# proyek_gempa_bumi.net
KiCad netlist of a schematic drawn in EAGLE
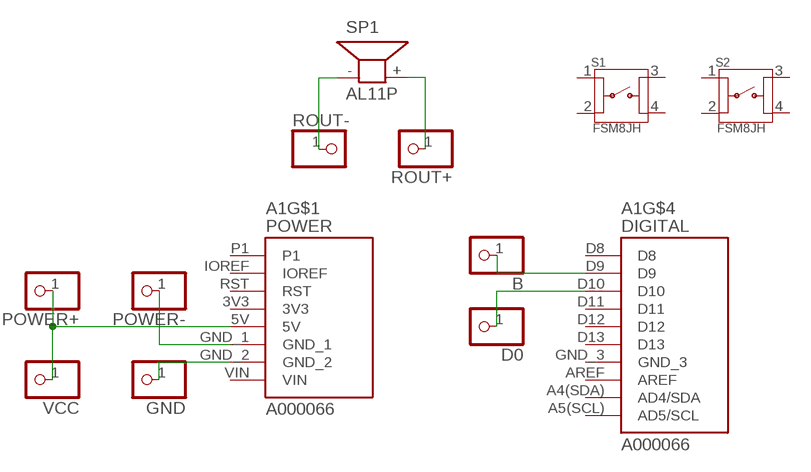
[diagram p0: schematic, sheet 1]

(export (version "E")
  (design (tool "Eeschema 10.0.6"))
  (components
    (comp (ref "A1")
      (value "A000066")
      (footprint "eagle-import:ARDUINO_A000066")
      (fields (field (name "MF") "Arduino") (field (name "MP") "ARDUINO UNO REV3"))
      (libsource (lib "eagle-import") (part "A000066"))
    )
    (comp (ref "B")
      (value "PINHD-1X1")
      (footprint "eagle-import:1X01")
      (libsource (lib "eagle-import") (part "PINHD-1X1"))
    )
    (comp (ref "D0")
      (value "PINHD-1X1")
      (footprint "eagle-import:1X01")
      (libsource (lib "eagle-import") (part "PINHD-1X1"))
    )
    (comp (ref "GND")
      (value "PINHD-1X1")
      (footprint "eagle-import:1X01")
      (libsource (lib "eagle-import") (part "PINHD-1X1"))
    )
    (comp (ref "POWER+")
      (value "PINHD-1X1")
      (footprint "eagle-import:1X01")
      (libsource (lib "eagle-import") (part "PINHD-1X1"))
    )
    (comp (ref "POWER-")
      (value "PINHD-1X1")
      (footprint "eagle-import:1X01")
      (libsource (lib "eagle-import") (part "PINHD-1X1"))
    )
    (comp (ref "ROUT+")
      (value "PINHD-1X1")
      (footprint "eagle-import:1X01")
      (libsource (lib "eagle-import") (part "PINHD-1X1"))
    )
    (comp (ref "ROUT-")
      (value "PINHD-1X1")
      (footprint "eagle-import:1X01")
      (libsource (lib "eagle-import") (part "PINHD-1X1"))
    )
    (comp (ref "S1")
      (value "FSM8JH")
      (footprint "eagle-import:SW_FSM8JH")
      (fields (field (name "MF") "TE Connectivity"))
      (libsource (lib "eagle-import") (part "FSM8JH"))
    )
    (comp (ref "S2")
      (value "FSM8JH")
      (footprint "eagle-import:SW_FSM8JH")
      (fields (field (name "MF") "TE Connectivity"))
      (libsource (lib "eagle-import") (part "FSM8JH"))
    )
    (comp (ref "SP1")
      (value "AL11P")
      (footprint "eagle-import:AL11P")
      (libsource (lib "eagle-import") (part "AL11P"))
    )
    (comp (ref "VCC")
      (value "PINHD-1X1")
      (footprint "eagle-import:1X01")
      (libsource (lib "eagle-import") (part "PINHD-1X1"))
    )
  )
  (nets
    (net (code "1") (name "/3V3") (class "Default")
      (node (ref "A1") (pin "3V3") (pinfunction "3V3_3V3") (pintype "power_in"))
    )
    (net (code "2") (name "/GND_3") (class "Default")
      (node (ref "A1") (pin "GND_3") (pinfunction "GND_3_GND_3") (pintype "power_in"))
    )
    (net (code "3") (name "/VIN") (class "Default")
      (node (ref "A1") (pin "VIN") (pinfunction "VIN_VIN") (pintype "power_in"))
    )
    (net (code "4") (name "Net-(A1-Pad5V)") (class "Default")
      (node (ref "A1") (pin "5V") (pinfunction "5V_5V") (pintype "power_in"))
      (node (ref "POWER+") (pin "1") (pinfunction "1_1") (pintype "passive"))
      (node (ref "VCC") (pin "1") (pinfunction "1_1") (pintype "passive"))
    )
    (net (code "5") (name "Net-(A1-PadD9)") (class "Default")
      (node (ref "A1") (pin "D9") (pinfunction "D9_D9") (pintype "bidirectional"))
      (node (ref "B") (pin "1") (pinfunction "1_1") (pintype "passive"))
    )
    (net (code "6") (name "Net-(A1-PadD10)") (class "Default")
      (node (ref "A1") (pin "D10") (pinfunction "D10_D10") (pintype "bidirectional"))
      (node (ref "D0") (pin "1") (pinfunction "1_1") (pintype "passive"))
    )
    (net (code "7") (name "Net-(A1-PadGND_1)") (class "Default")
      (node (ref "A1") (pin "GND_1") (pinfunction "GND_1_GND_1") (pintype "power_in"))
      (node (ref "POWER-") (pin "1") (pinfunction "1_1") (pintype "passive"))
    )
    (net (code "8") (name "Net-(A1-PadGND_2)") (class "Default")
      (node (ref "A1") (pin "GND_2") (pinfunction "GND_2_GND_2") (pintype "power_in"))
      (node (ref "GND") (pin "1") (pinfunction "1_1") (pintype "passive"))
    )
    (net (code "9") (name "Net-(SP1-1)") (class "Default")
      (node (ref "ROUT-") (pin "1") (pinfunction "1_1") (pintype "passive"))
      (node (ref "SP1") (pin "-") (pinfunction "1_-") (pintype "passive"))
    )
    (net (code "10") (name "Net-(SP1-2)") (class "Default")
      (node (ref "ROUT+") (pin "1") (pinfunction "1_1") (pintype "passive"))
      (node (ref "SP1") (pin "+") (pinfunction "2_+") (pintype "passive"))
    )
    (net (code "11") (name "unconnected-(A1-PadAREF)") (class "Default")
      (node (ref "A1") (pin "AREF") (pinfunction "AREF_AREF") (pintype "bidirectional"))
    )
    (net (code "12") (name "unconnected-(A1-PadD8)") (class "Default")
      (node (ref "A1") (pin "D8") (pinfunction "D8_D8") (pintype "bidirectional"))
    )
    (net (code "13") (name "unconnected-(A1-PadD11)") (class "Default")
      (node (ref "A1") (pin "D11") (pinfunction "D11_D11") (pintype "bidirectional"))
    )
    (net (code "14") (name "unconnected-(A1-PadD12)") (class "Default")
      (node (ref "A1") (pin "D12") (pinfunction "D12_D12") (pintype "bidirectional"))
    )
    (net (code "15") (name "unconnected-(A1-PadD13)") (class "Default")
      (node (ref "A1") (pin "D13") (pinfunction "D13_D13") (pintype "bidirectional"))
    )
    (net (code "16") (name "unconnected-(A1-PadIOREF)") (class "Default")
      (node (ref "A1") (pin "IOREF") (pinfunction "IOREF_IOREF") (pintype "bidirectional"))
    )
    (net (code "17") (name "unconnected-(A1-PadP1)") (class "Default")
      (node (ref "A1") (pin "P1") (pinfunction "P1_P1") (pintype "bidirectional"))
    )
    (net (code "18") (name "unconnected-(A1-PadRST)") (class "Default")
      (node (ref "A1") (pin "RST") (pinfunction "RST_RST") (pintype "bidirectional"))
    )
    (net (code "19") (name "unconnected-(A1D-AD4{slash}SDA-PadA4(SDA))") (class "Default")
      (node (ref "A1") (pin "A4(SDA)") (pinfunction "AD4/SDA_A4(SDA)") (pintype "bidirectional"))
    )
    (net (code "20") (name "unconnected-(A1D-AD5{slash}SCL-PadA5(SCL))") (class "Default")
      (node (ref "A1") (pin "A5(SCL)") (pinfunction "AD5/SCL_A5(SCL)") (pintype "bidirectional"))
    )
    (net (code "21") (name "unconnected-(S1-Pad1)") (class "Default")
      (node (ref "S1") (pin "1") (pinfunction "1_1") (pintype "passive"))
    )
    (net (code "22") (name "unconnected-(S1-Pad2)") (class "Default")
      (node (ref "S1") (pin "2") (pinfunction "2_2") (pintype "passive"))
    )
    (net (code "23") (name "unconnected-(S1-Pad3)") (class "Default")
      (node (ref "S1") (pin "3") (pinfunction "3_3") (pintype "passive"))
    )
    (net (code "24") (name "unconnected-(S1-Pad4)") (class "Default")
      (node (ref "S1") (pin "4") (pinfunction "4_4") (pintype "passive"))
    )
    (net (code "25") (name "unconnected-(S2-Pad1)") (class "Default")
      (node (ref "S2") (pin "1") (pinfunction "1_1") (pintype "passive"))
    )
    (net (code "26") (name "unconnected-(S2-Pad2)") (class "Default")
      (node (ref "S2") (pin "2") (pinfunction "2_2") (pintype "passive"))
    )
    (net (code "27") (name "unconnected-(S2-Pad3)") (class "Default")
      (node (ref "S2") (pin "3") (pinfunction "3_3") (pintype "passive"))
    )
    (net (code "28") (name "unconnected-(S2-Pad4)") (class "Default")
      (node (ref "S2") (pin "4") (pinfunction "4_4") (pintype "passive"))
    )
  )
)
